# plcc44-adapter.net
KiCad netlist of a schematic drawn in EAGLE
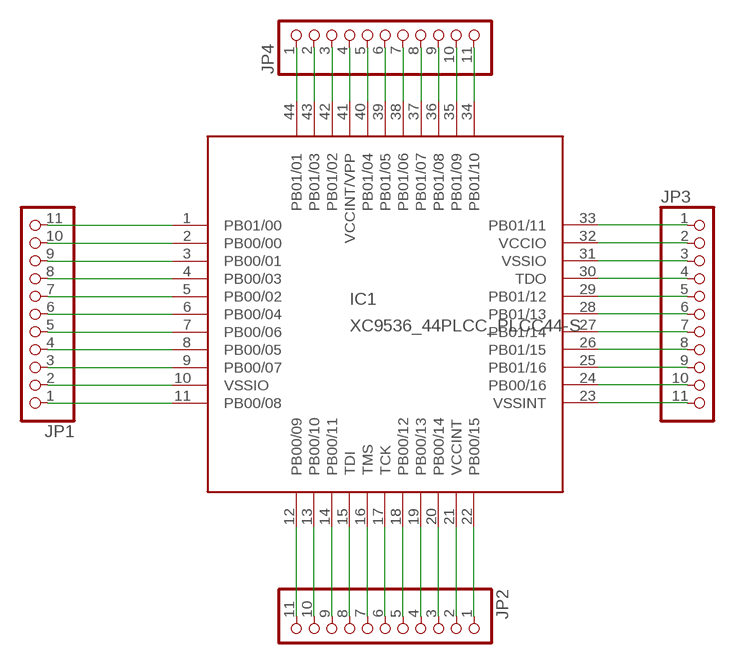
[diagram p0: schematic, sheet 1]

(export (version "E")
  (design (tool "Eeschema 10.0.6"))
  (components
    (comp (ref "IC1")
      (value "XC9536_44PLCC_PLCC44-S")
      (footprint "eagle-import:PLCC-S44")
      (libsource (lib "eagle-import") (part "XC9536_44PLCC_PLCC44-S"))
    )
    (comp (ref "JP1")
      (value "PINHD-1X11")
      (footprint "eagle-import:1X11")
      (libsource (lib "eagle-import") (part "PINHD-1X11"))
    )
    (comp (ref "JP2")
      (value "PINHD-1X11")
      (footprint "eagle-import:1X11")
      (libsource (lib "eagle-import") (part "PINHD-1X11"))
    )
    (comp (ref "JP3")
      (value "PINHD-1X11")
      (footprint "eagle-import:1X11")
      (libsource (lib "eagle-import") (part "PINHD-1X11"))
    )
    (comp (ref "JP4")
      (value "PINHD-1X11")
      (footprint "eagle-import:1X11")
      (libsource (lib "eagle-import") (part "PINHD-1X11"))
    )
  )
  (nets
    (net (code "1") (name "Net-(IC1-PB00{slash}00)") (class "Default")
      (node (ref "IC1") (pin "2") (pinfunction "PB00/00_2") (pintype "bidirectional"))
      (node (ref "JP1") (pin "10") (pinfunction "10_10") (pintype "passive"))
    )
    (net (code "2") (name "Net-(IC1-PB00{slash}01)") (class "Default")
      (node (ref "IC1") (pin "3") (pinfunction "PB00/01_3") (pintype "bidirectional"))
      (node (ref "JP1") (pin "9") (pinfunction "9_9") (pintype "passive"))
    )
    (net (code "3") (name "Net-(IC1-PB00{slash}02)") (class "Default")
      (node (ref "IC1") (pin "5") (pinfunction "PB00/02_5") (pintype "bidirectional"))
      (node (ref "JP1") (pin "7") (pinfunction "7_7") (pintype "passive"))
    )
    (net (code "4") (name "Net-(IC1-PB00{slash}03)") (class "Default")
      (node (ref "IC1") (pin "4") (pinfunction "PB00/03_4") (pintype "bidirectional"))
      (node (ref "JP1") (pin "8") (pinfunction "8_8") (pintype "passive"))
    )
    (net (code "5") (name "Net-(IC1-PB00{slash}04)") (class "Default")
      (node (ref "IC1") (pin "6") (pinfunction "PB00/04_6") (pintype "bidirectional"))
      (node (ref "JP1") (pin "6") (pinfunction "6_6") (pintype "passive"))
    )
    (net (code "6") (name "Net-(IC1-PB00{slash}05)") (class "Default")
      (node (ref "IC1") (pin "8") (pinfunction "PB00/05_8") (pintype "bidirectional"))
      (node (ref "JP1") (pin "4") (pinfunction "4_4") (pintype "passive"))
    )
    (net (code "7") (name "Net-(IC1-PB00{slash}06)") (class "Default")
      (node (ref "IC1") (pin "7") (pinfunction "PB00/06_7") (pintype "bidirectional"))
      (node (ref "JP1") (pin "5") (pinfunction "5_5") (pintype "passive"))
    )
    (net (code "8") (name "Net-(IC1-PB00{slash}07)") (class "Default")
      (node (ref "IC1") (pin "9") (pinfunction "PB00/07_9") (pintype "bidirectional"))
      (node (ref "JP1") (pin "3") (pinfunction "3_3") (pintype "passive"))
    )
    (net (code "9") (name "Net-(IC1-PB00{slash}08)") (class "Default")
      (node (ref "IC1") (pin "11") (pinfunction "PB00/08_11") (pintype "bidirectional"))
      (node (ref "JP1") (pin "1") (pinfunction "1_1") (pintype "passive"))
    )
    (net (code "10") (name "Net-(IC1-PB00{slash}09)") (class "Default")
      (node (ref "IC1") (pin "12") (pinfunction "PB00/09_12") (pintype "bidirectional"))
      (node (ref "JP2") (pin "11") (pinfunction "11_11") (pintype "passive"))
    )
    (net (code "11") (name "Net-(IC1-PB00{slash}10)") (class "Default")
      (node (ref "IC1") (pin "13") (pinfunction "PB00/10_13") (pintype "bidirectional"))
      (node (ref "JP2") (pin "10") (pinfunction "10_10") (pintype "passive"))
    )
    (net (code "12") (name "Net-(IC1-PB00{slash}11)") (class "Default")
      (node (ref "IC1") (pin "14") (pinfunction "PB00/11_14") (pintype "bidirectional"))
      (node (ref "JP2") (pin "9") (pinfunction "9_9") (pintype "passive"))
    )
    (net (code "13") (name "Net-(IC1-PB00{slash}12)") (class "Default")
      (node (ref "IC1") (pin "18") (pinfunction "PB00/12_18") (pintype "bidirectional"))
      (node (ref "JP2") (pin "5") (pinfunction "5_5") (pintype "passive"))
    )
    (net (code "14") (name "Net-(IC1-PB00{slash}13)") (class "Default")
      (node (ref "IC1") (pin "19") (pinfunction "PB00/13_19") (pintype "bidirectional"))
      (node (ref "JP2") (pin "4") (pinfunction "4_4") (pintype "passive"))
    )
    (net (code "15") (name "Net-(IC1-PB00{slash}14)") (class "Default")
      (node (ref "IC1") (pin "20") (pinfunction "PB00/14_20") (pintype "bidirectional"))
      (node (ref "JP2") (pin "3") (pinfunction "3_3") (pintype "passive"))
    )
    (net (code "16") (name "Net-(IC1-PB00{slash}15)") (class "Default")
      (node (ref "IC1") (pin "22") (pinfunction "PB00/15_22") (pintype "bidirectional"))
      (node (ref "JP2") (pin "1") (pinfunction "1_1") (pintype "passive"))
    )
    (net (code "17") (name "Net-(IC1-PB00{slash}16)") (class "Default")
      (node (ref "IC1") (pin "24") (pinfunction "PB00/16_24") (pintype "bidirectional"))
      (node (ref "JP3") (pin "10") (pinfunction "10_10") (pintype "passive"))
    )
    (net (code "18") (name "Net-(IC1-PB01{slash}00)") (class "Default")
      (node (ref "IC1") (pin "1") (pinfunction "PB01/00_1") (pintype "bidirectional"))
      (node (ref "JP1") (pin "11") (pinfunction "11_11") (pintype "passive"))
    )
    (net (code "19") (name "Net-(IC1-PB01{slash}01)") (class "Default")
      (node (ref "IC1") (pin "44") (pinfunction "PB01/01_44") (pintype "bidirectional"))
      (node (ref "JP4") (pin "1") (pinfunction "1_1") (pintype "passive"))
    )
    (net (code "20") (name "Net-(IC1-PB01{slash}02)") (class "Default")
      (node (ref "IC1") (pin "42") (pinfunction "PB01/02_42") (pintype "bidirectional"))
      (node (ref "JP4") (pin "3") (pinfunction "3_3") (pintype "passive"))
    )
    (net (code "21") (name "Net-(IC1-PB01{slash}03)") (class "Default")
      (node (ref "IC1") (pin "43") (pinfunction "PB01/03_43") (pintype "bidirectional"))
      (node (ref "JP4") (pin "2") (pinfunction "2_2") (pintype "passive"))
    )
    (net (code "22") (name "Net-(IC1-PB01{slash}04)") (class "Default")
      (node (ref "IC1") (pin "40") (pinfunction "PB01/04_40") (pintype "bidirectional"))
      (node (ref "JP4") (pin "5") (pinfunction "5_5") (pintype "passive"))
    )
    (net (code "23") (name "Net-(IC1-PB01{slash}05)") (class "Default")
      (node (ref "IC1") (pin "39") (pinfunction "PB01/05_39") (pintype "bidirectional"))
      (node (ref "JP4") (pin "6") (pinfunction "6_6") (pintype "passive"))
    )
    (net (code "24") (name "Net-(IC1-PB01{slash}06)") (class "Default")
      (node (ref "IC1") (pin "38") (pinfunction "PB01/06_38") (pintype "bidirectional"))
      (node (ref "JP4") (pin "7") (pinfunction "7_7") (pintype "passive"))
    )
    (net (code "25") (name "Net-(IC1-PB01{slash}07)") (class "Default")
      (node (ref "IC1") (pin "37") (pinfunction "PB01/07_37") (pintype "bidirectional"))
      (node (ref "JP4") (pin "8") (pinfunction "8_8") (pintype "passive"))
    )
    (net (code "26") (name "Net-(IC1-PB01{slash}08)") (class "Default")
      (node (ref "IC1") (pin "36") (pinfunction "PB01/08_36") (pintype "bidirectional"))
      (node (ref "JP4") (pin "9") (pinfunction "9_9") (pintype "passive"))
    )
    (net (code "27") (name "Net-(IC1-PB01{slash}09)") (class "Default")
      (node (ref "IC1") (pin "35") (pinfunction "PB01/09_35") (pintype "bidirectional"))
      (node (ref "JP4") (pin "10") (pinfunction "10_10") (pintype "passive"))
    )
    (net (code "28") (name "Net-(IC1-PB01{slash}10)") (class "Default")
      (node (ref "IC1") (pin "34") (pinfunction "PB01/10_34") (pintype "bidirectional"))
      (node (ref "JP4") (pin "11") (pinfunction "11_11") (pintype "passive"))
    )
    (net (code "29") (name "Net-(IC1-PB01{slash}11)") (class "Default")
      (node (ref "IC1") (pin "33") (pinfunction "PB01/11_33") (pintype "bidirectional"))
      (node (ref "JP3") (pin "1") (pinfunction "1_1") (pintype "passive"))
    )
    (net (code "30") (name "Net-(IC1-PB01{slash}12)") (class "Default")
      (node (ref "IC1") (pin "29") (pinfunction "PB01/12_29") (pintype "bidirectional"))
      (node (ref "JP3") (pin "5") (pinfunction "5_5") (pintype "passive"))
    )
    (net (code "31") (name "Net-(IC1-PB01{slash}13)") (class "Default")
      (node (ref "IC1") (pin "28") (pinfunction "PB01/13_28") (pintype "bidirectional"))
      (node (ref "JP3") (pin "6") (pinfunction "6_6") (pintype "passive"))
    )
    (net (code "32") (name "Net-(IC1-PB01{slash}14)") (class "Default")
      (node (ref "IC1") (pin "27") (pinfunction "PB01/14_27") (pintype "bidirectional"))
      (node (ref "JP3") (pin "7") (pinfunction "7_7") (pintype "passive"))
    )
    (net (code "33") (name "Net-(IC1-PB01{slash}15)") (class "Default")
      (node (ref "IC1") (pin "26") (pinfunction "PB01/15_26") (pintype "bidirectional"))
      (node (ref "JP3") (pin "8") (pinfunction "8_8") (pintype "passive"))
    )
    (net (code "34") (name "Net-(IC1-PB01{slash}16)") (class "Default")
      (node (ref "IC1") (pin "25") (pinfunction "PB01/16_25") (pintype "bidirectional"))
      (node (ref "JP3") (pin "9") (pinfunction "9_9") (pintype "passive"))
    )
    (net (code "35") (name "Net-(IC1-TCK)") (class "Default")
      (node (ref "IC1") (pin "17") (pinfunction "TCK_17") (pintype "input"))
      (node (ref "JP2") (pin "6") (pinfunction "6_6") (pintype "passive"))
    )
    (net (code "36") (name "Net-(IC1-TDI)") (class "Default")
      (node (ref "IC1") (pin "15") (pinfunction "TDI_15") (pintype "input"))
      (node (ref "JP2") (pin "8") (pinfunction "8_8") (pintype "passive"))
    )
    (net (code "37") (name "Net-(IC1-TDO)") (class "Default")
      (node (ref "IC1") (pin "30") (pinfunction "TDO_30") (pintype "output"))
      (node (ref "JP3") (pin "4") (pinfunction "4_4") (pintype "passive"))
    )
    (net (code "38") (name "Net-(IC1-TMS)") (class "Default")
      (node (ref "IC1") (pin "16") (pinfunction "TMS_16") (pintype "input"))
      (node (ref "JP2") (pin "7") (pinfunction "7_7") (pintype "passive"))
    )
    (net (code "39") (name "Net-(IC1-VCCINT)") (class "Default")
      (node (ref "IC1") (pin "21") (pinfunction "VCCINT_21") (pintype "power_in"))
      (node (ref "JP2") (pin "2") (pinfunction "2_2") (pintype "passive"))
    )
    (net (code "40") (name "Net-(IC1-VCCINT{slash}VPP)") (class "Default")
      (node (ref "IC1") (pin "41") (pinfunction "VCCINT/VPP_41") (pintype "input"))
      (node (ref "JP4") (pin "4") (pinfunction "4_4") (pintype "passive"))
    )
    (net (code "41") (name "Net-(IC1-VCCIO)") (class "Default")
      (node (ref "IC1") (pin "32") (pinfunction "VCCIO_32") (pintype "power_in"))
      (node (ref "JP3") (pin "2") (pinfunction "2_2") (pintype "passive"))
    )
    (net (code "42") (name "Net-(IC1-VSSINT)") (class "Default")
      (node (ref "IC1") (pin "23") (pinfunction "VSSINT_23") (pintype "power_in"))
      (node (ref "JP3") (pin "11") (pinfunction "11_11") (pintype "passive"))
    )
    (net (code "43") (name "Net-(IC1-VSSIO-Pad10)") (class "Default")
      (node (ref "IC1") (pin "10") (pinfunction "VSSIO_10") (pintype "power_in"))
      (node (ref "JP1") (pin "2") (pinfunction "2_2") (pintype "passive"))
    )
    (net (code "44") (name "Net-(IC1-VSSIO-Pad31)") (class "Default")
      (node (ref "IC1") (pin "31") (pinfunction "VSSIO_31") (pintype "power_in"))
      (node (ref "JP3") (pin "3") (pinfunction "3_3") (pintype "passive"))
    )
  )
)
